# 20_Power_DC_IN.net
KiCad netlist of a schematic drawn in Altium Designer
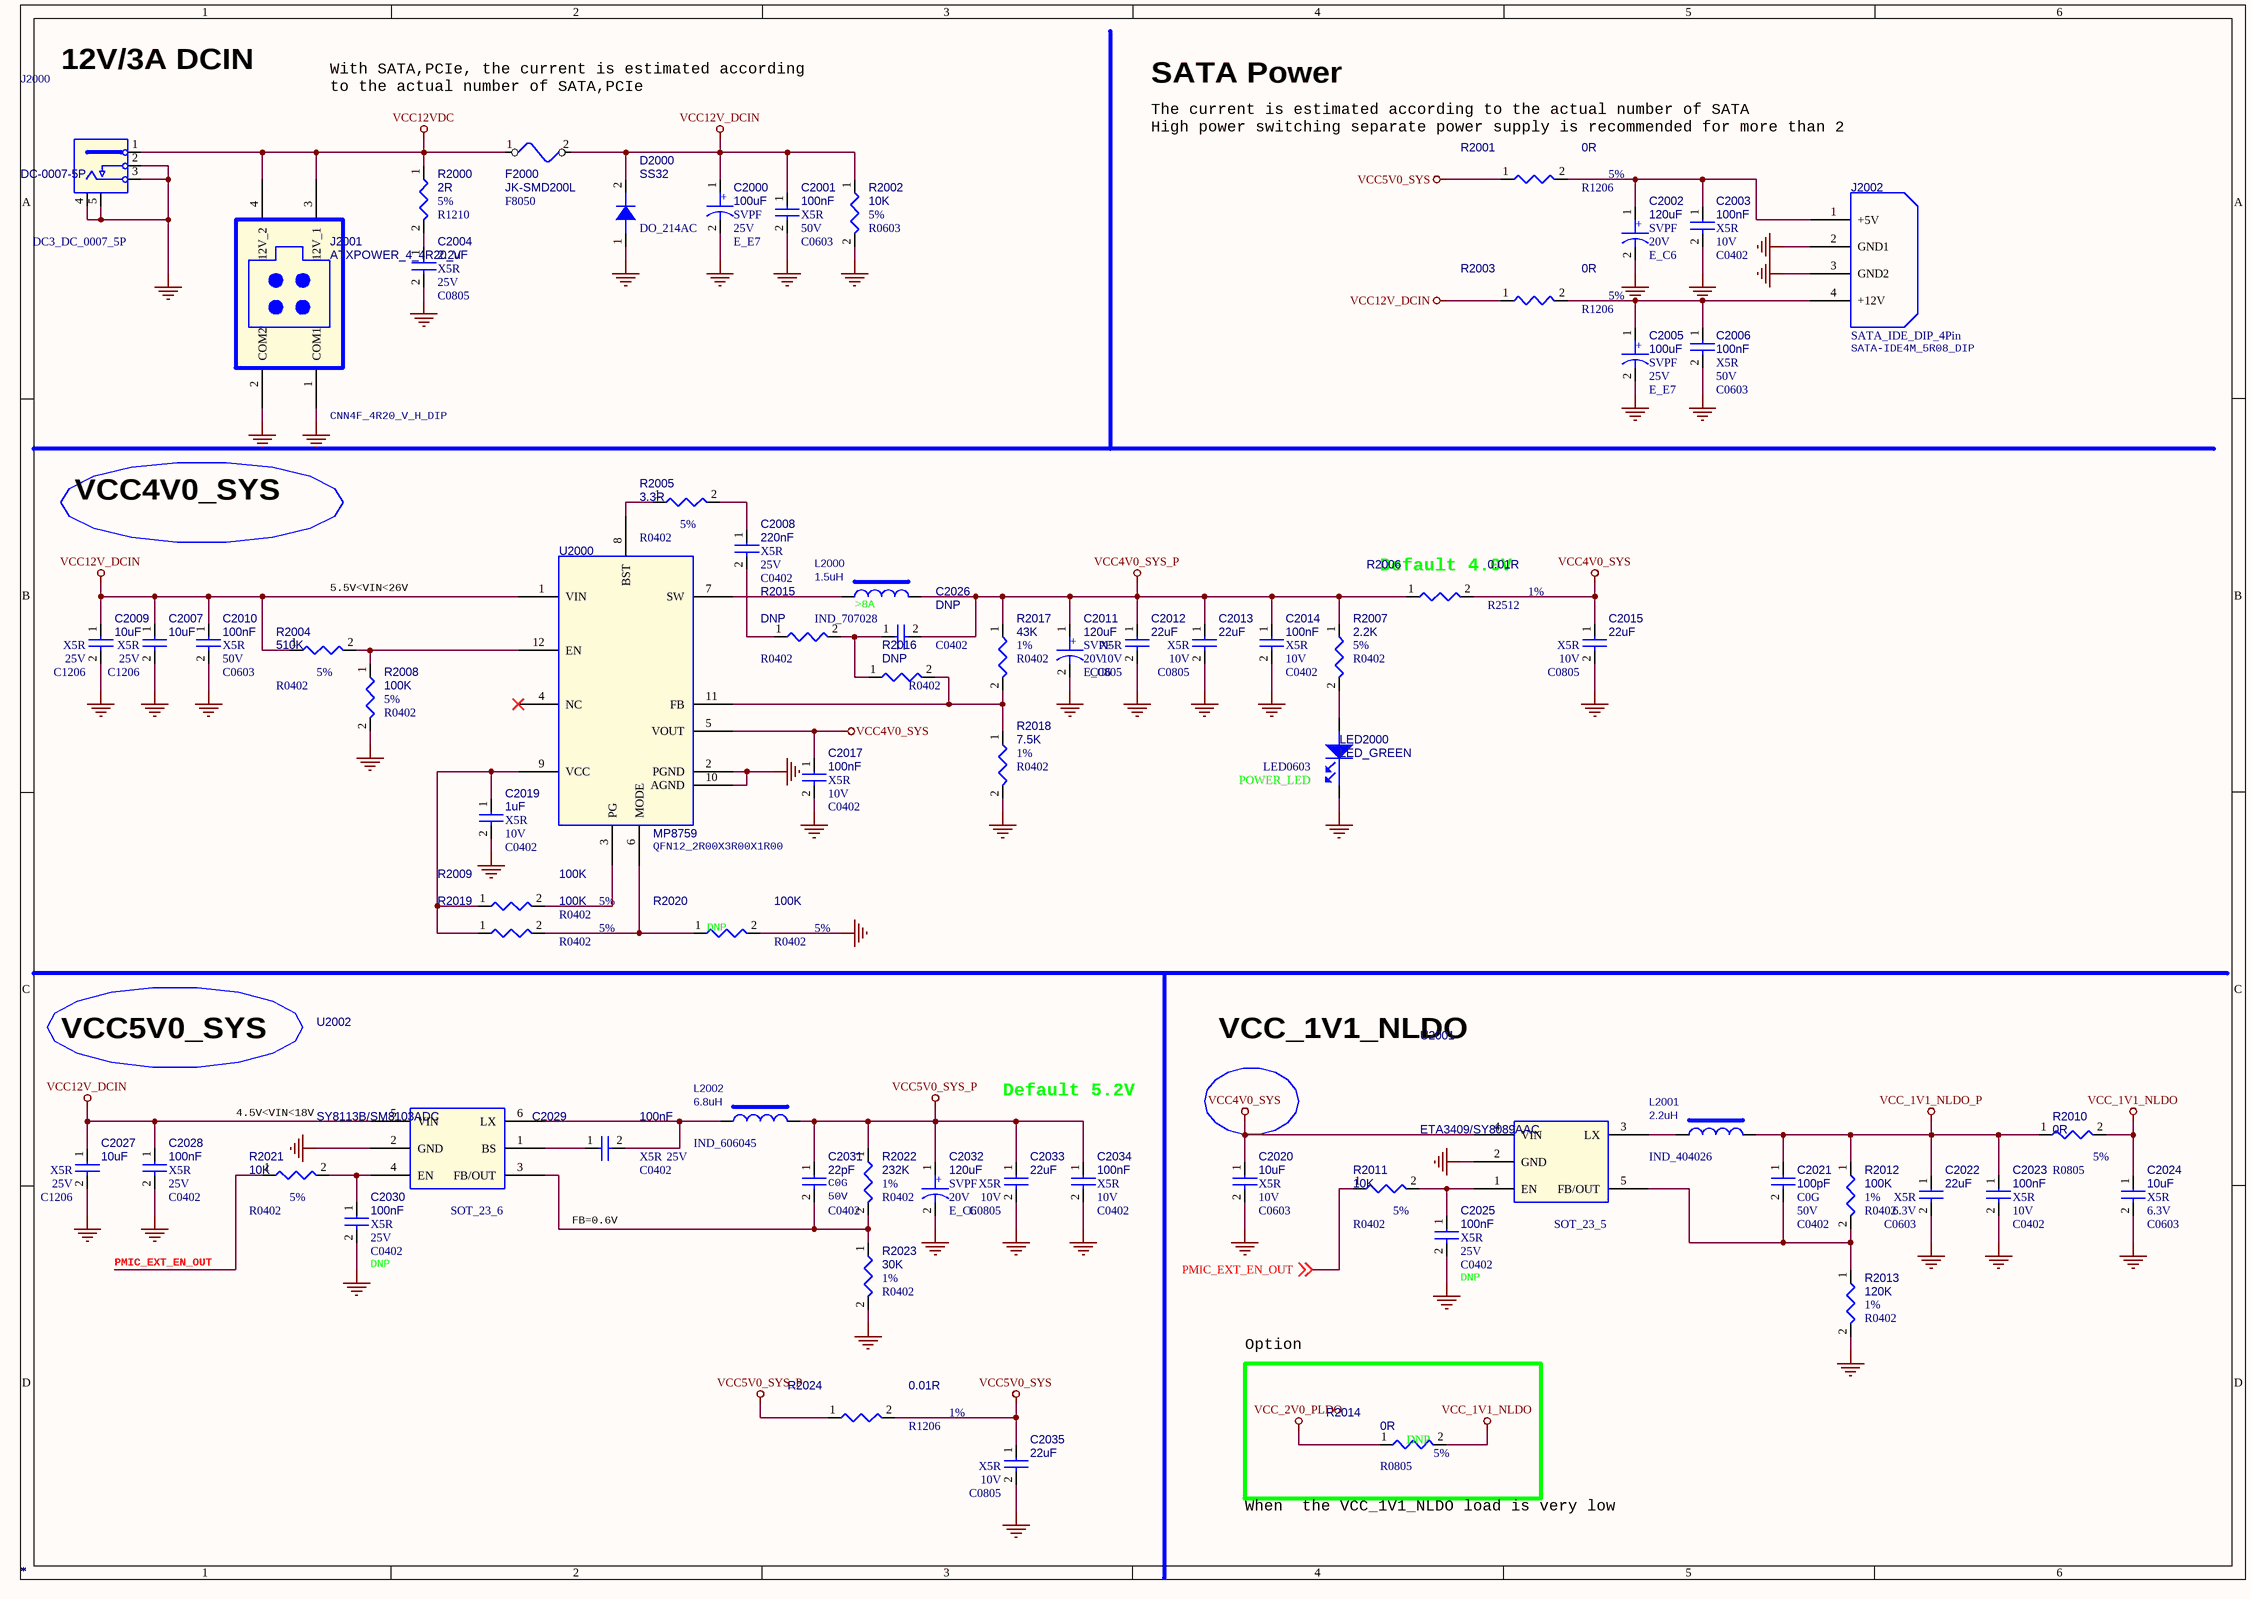
[diagram p0: 20.Power_DC IN.SchDoc]

(export (version "E")
  (design (tool "Eeschema 10.0.6"))
  (components
    (comp (ref "C2000")
      (value "*")
      (footprint "E_E7")
      (description "100uF,25V,24mR,SVPF")
      (fields
        (field (name "VOLTAGE") "25V")
        (field (name "DIELECTRIC") "SVPF")
        (field (name "PCB FOOTPRINT") "E_E7")
        (field (name "TOLERANCE") "20%")
        (field (name "MANUFACTURER") "Panasonic")
        (field (name "ALTIUM_UNNAMED_1") "100uF")
        (field (name "CREATED BY") "JJJ")
      )
      (libsource (lib "*") (part "CAP"))
    )
    (comp (ref "C2001")
      (value "*")
      (footprint "C0603")
      (description "cap,100.00nF,+/-10%,50V,X5R,C0603")
      (fields
        (field (name "VOLTAGE") "50V")
        (field (name "PCB FOOTPRINT") "C0603")
        (field (name "DIELECTRIC") "X5R")
        (field (name "MANUFACTURER") "TDK")
        (field (name "TOLERANCE") "10%")
        (field (name "ALTIUM_UNNAMED_1") "100nF")
        (field (name "CREATED BY") "JJJ")
      )
      (libsource (lib "*") (part "CAP NP"))
    )
    (comp (ref "C2002")
      (value "*")
      (footprint "E_C6")
      (description "120uF,20V,25mR,SVPF")
      (fields
        (field (name "VOLTAGE") "20V")
        (field (name "DIELECTRIC") "SVPF")
        (field (name "PCB FOOTPRINT") "E_C6")
        (field (name "MANUFACTURER") "Panasonic")
        (field (name "TOLERANCE") "20%")
        (field (name "ALTIUM_UNNAMED_1") "120uF")
        (field (name "CREATED BY") "JJJ")
      )
      (libsource (lib "*") (part "CAP"))
    )
    (comp (ref "C2003")
      (value "*")
      (footprint "C0402")
      (description "cap,100.00nF,+/-10%,10V,X5R,C0402")
      (fields
        (field (name "VOLTAGE") "10V")
        (field (name "PCB FOOTPRINT") "C0402")
        (field (name "DIELECTRIC") "X5R")
        (field (name "TOLERANCE") "10%")
        (field (name "MANUFACTURER") "TDK")
        (field (name "ALTIUM_UNNAMED_1") "100nF")
        (field (name "CREATED BY") "JJJ")
      )
      (libsource (lib "*") (part "CAP NP"))
    )
    (comp (ref "C2004")
      (value "*")
      (footprint "C0805")
      (description "cap,2.20uF,+/-10%,25V,X5R,C0805")
      (fields
        (field (name "VOLTAGE") "25V")
        (field (name "PCB FOOTPRINT") "C0805")
        (field (name "DIELECTRIC") "X5R")
        (field (name "TOLERANCE") "10%")
        (field (name "MANUFACTURER") "TDK")
        (field (name "ALTIUM_UNNAMED_1") "2.2uF")
        (field (name "CREATED BY") "JJJ")
      )
      (libsource (lib "*") (part "CAP NP"))
    )
    (comp (ref "C2005")
      (value "*")
      (footprint "E_E7")
      (description "100uF,25V,24mR,SVPF")
      (fields
        (field (name "VOLTAGE") "25V")
        (field (name "DIELECTRIC") "SVPF")
        (field (name "PCB FOOTPRINT") "E_E7")
        (field (name "MANUFACTURER") "Panasonic")
        (field (name "TOLERANCE") "20%")
        (field (name "ALTIUM_UNNAMED_1") "100uF")
        (field (name "CREATED BY") "JJJ")
      )
      (libsource (lib "*") (part "CAP"))
    )
    (comp (ref "C2006")
      (value "*")
      (footprint "C0603")
      (description "cap,100.00nF,+/-10%,50V,X5R,C0603")
      (fields
        (field (name "VOLTAGE") "50V")
        (field (name "PCB FOOTPRINT") "C0603")
        (field (name "DIELECTRIC") "X5R")
        (field (name "MANUFACTURER") "TDK")
        (field (name "TOLERANCE") "10%")
        (field (name "ALTIUM_UNNAMED_1") "100nF")
        (field (name "CREATED BY") "JJJ")
      )
      (libsource (lib "*") (part "CAP NP"))
    )
    (comp (ref "C2007")
      (value "*")
      (footprint "C1206")
      (description "cap,10.00uF,+/-10%,25V,X5R,C1206")
      (fields
        (field (name "VOLTAGE") "25V")
        (field (name "PCB FOOTPRINT") "C1206")
        (field (name "DIELECTRIC") "X5R")
        (field (name "MANUFACTURER") "TDK")
        (field (name "TOLERANCE") "10%")
        (field (name "ALTIUM_UNNAMED_1") "10uF")
        (field (name "CREATED BY") "JJJ")
      )
      (libsource (lib "*") (part "CAP NP"))
    )
    (comp (ref "C2008")
      (value "*")
      (footprint "C0402")
      (description "cap,220.00nF,+/-10%,25V,X5R,C0402")
      (fields
        (field (name "VOLTAGE") "25V")
        (field (name "PCB FOOTPRINT") "C0402")
        (field (name "DIELECTRIC") "X5R")
        (field (name "MANUFACTURER") "TDK")
        (field (name "TOLERANCE") "10%")
        (field (name "ALTIUM_UNNAMED_1") "220nF")
        (field (name "CREATED BY") "JJJ")
      )
      (libsource (lib "*") (part "CAP NP"))
    )
    (comp (ref "C2009")
      (value "*")
      (footprint "C1206")
      (description "cap,10.00uF,+/-10%,25V,X5R,C1206")
      (fields
        (field (name "VOLTAGE") "25V")
        (field (name "PCB FOOTPRINT") "C1206")
        (field (name "DIELECTRIC") "X5R")
        (field (name "MANUFACTURER") "TDK")
        (field (name "TOLERANCE") "10%")
        (field (name "ALTIUM_UNNAMED_1") "10uF")
        (field (name "CREATED BY") "JJJ")
      )
      (libsource (lib "*") (part "CAP NP"))
    )
    (comp (ref "C2010")
      (value "*")
      (footprint "C0603")
      (description "cap,100.00nF,+/-10%,50V,X5R,C0603")
      (fields
        (field (name "VOLTAGE") "50V")
        (field (name "PCB FOOTPRINT") "C0603")
        (field (name "DIELECTRIC") "X5R")
        (field (name "MANUFACTURER") "TDK")
        (field (name "TOLERANCE") "10%")
        (field (name "ALTIUM_UNNAMED_1") "100nF")
        (field (name "CREATED BY") "JJJ")
      )
      (libsource (lib "*") (part "CAP NP"))
    )
    (comp (ref "C2011")
      (value "*")
      (footprint "E_C6")
      (description "120uF,20V,25mR,SVPF")
      (fields
        (field (name "VOLTAGE") "20V")
        (field (name "DIELECTRIC") "SVPF")
        (field (name "PCB FOOTPRINT") "E_C6")
        (field (name "MANUFACTURER") "Panasonic")
        (field (name "TOLERANCE") "20%")
        (field (name "ALTIUM_UNNAMED_1") "120uF")
        (field (name "CREATED BY") "JJJ")
      )
      (libsource (lib "*") (part "CAP"))
    )
    (comp (ref "C2012")
      (value "*")
      (footprint "C0805")
      (description "cap,22.00uF,+/-10%,10V,X5R,C0805")
      (fields
        (field (name "VOLTAGE") "10V")
        (field (name "PCB FOOTPRINT") "C0805")
        (field (name "DIELECTRIC") "X5R")
        (field (name "TOLERANCE") "10%")
        (field (name "MANUFACTURER") "TDK")
        (field (name "ALTIUM_UNNAMED_1") "22uF")
        (field (name "CREATED BY") "JJJ")
      )
      (libsource (lib "*") (part "CAP NP"))
    )
    (comp (ref "C2013")
      (value "*")
      (footprint "C0805")
      (description "cap,22.00uF,+/-10%,10V,X5R,C0805")
      (fields
        (field (name "VOLTAGE") "10V")
        (field (name "PCB FOOTPRINT") "C0805")
        (field (name "DIELECTRIC") "X5R")
        (field (name "MANUFACTURER") "TDK")
        (field (name "TOLERANCE") "10%")
        (field (name "ALTIUM_UNNAMED_1") "22uF")
        (field (name "CREATED BY") "JJJ")
      )
      (libsource (lib "*") (part "CAP NP"))
    )
    (comp (ref "C2014")
      (value "*")
      (footprint "C0402")
      (description "cap,100.00nF,+/-10%,10V,X5R,C0402")
      (fields
        (field (name "VOLTAGE") "10V")
        (field (name "PCB FOOTPRINT") "C0402")
        (field (name "DIELECTRIC") "X5R")
        (field (name "MANUFACTURER") "TDK")
        (field (name "TOLERANCE") "10%")
        (field (name "ALTIUM_UNNAMED_1") "100nF")
        (field (name "CREATED BY") "JJJ")
      )
      (libsource (lib "*") (part "CAP NP"))
    )
    (comp (ref "C2015")
      (value "*")
      (footprint "C0805")
      (description "cap,22.00uF,+/-10%,10V,X5R,C0805")
      (fields
        (field (name "VOLTAGE") "10V")
        (field (name "PCB FOOTPRINT") "C0805")
        (field (name "DIELECTRIC") "X5R")
        (field (name "MANUFACTURER") "TDK")
        (field (name "TOLERANCE") "10%")
        (field (name "ALTIUM_UNNAMED_1") "22uF")
        (field (name "CREATED BY") "JJJ")
      )
      (libsource (lib "*") (part "CAP NP"))
    )
    (comp (ref "C2017")
      (value "*")
      (footprint "C0402")
      (description "cap,100.00nF,+/-10%,10V,X5R,C0402")
      (fields
        (field (name "VOLTAGE") "10V")
        (field (name "PCB FOOTPRINT") "C0402")
        (field (name "DIELECTRIC") "X5R")
        (field (name "TOLERANCE") "10%")
        (field (name "MANUFACTURER") "TDK")
        (field (name "ALTIUM_UNNAMED_1") "100nF")
        (field (name "CREATED BY") "JJJ")
      )
      (libsource (lib "*") (part "CAP NP"))
    )
    (comp (ref "C2019")
      (value "*")
      (footprint "C0402")
      (description "cap,1.00uF,+/-10%,10V,X5R,C0402")
      (fields
        (field (name "VOLTAGE") "10V")
        (field (name "PCB FOOTPRINT") "C0402")
        (field (name "DIELECTRIC") "X5R")
        (field (name "MANUFACTURER") "TDK")
        (field (name "TOLERANCE") "10%")
        (field (name "ALTIUM_UNNAMED_1") "1uF")
        (field (name "CREATED BY") "JJJ")
      )
      (libsource (lib "*") (part "CAP NP"))
    )
    (comp (ref "C2020")
      (value "*")
      (footprint "C0603")
      (description "cap,10.00uF,+/-10%,10V,X5R,C0603")
      (fields
        (field (name "VOLTAGE") "10V")
        (field (name "PCB FOOTPRINT") "C0603")
        (field (name "DIELECTRIC") "X5R")
        (field (name "MANUFACTURER") "TDK")
        (field (name "TOLERANCE") "10%")
        (field (name "ALTIUM_UNNAMED_1") "10uF")
        (field (name "CREATED BY") "JJJ")
      )
      (libsource (lib "*") (part "CAP NP"))
    )
    (comp (ref "C2021")
      (value "*")
      (footprint "C0402")
      (description "cap,100.00pF,+/-10%,50V,C0G,C0402")
      (fields
        (field (name "VOLTAGE") "50V")
        (field (name "PCB FOOTPRINT") "C0402")
        (field (name "DIELECTRIC") "C0G")
        (field (name "MANUFACTURER") "TDK")
        (field (name "TOLERANCE") "10%")
        (field (name "ALTIUM_UNNAMED_1") "100pF")
        (field (name "CREATED BY") "JJJ")
      )
      (libsource (lib "*") (part "CAP NP"))
    )
    (comp (ref "C2022")
      (value "*")
      (footprint "C0603")
      (description "cap,22.00uF,+/-20%,6.3V,X5R,C0603")
      (fields
        (field (name "VOLTAGE") "6.3V")
        (field (name "PCB FOOTPRINT") "C0603")
        (field (name "DIELECTRIC") "X5R")
        (field (name "TOLERANCE") "20%")
        (field (name "MANUFACTURER") "TDK")
        (field (name "ALTIUM_UNNAMED_1") "22uF")
        (field (name "CREATED BY") "JJJ")
      )
      (libsource (lib "*") (part "CAP NP"))
    )
    (comp (ref "C2023")
      (value "*")
      (footprint "C0402")
      (description "cap,100.00nF,+/-10%,10V,X5R,C0402")
      (fields
        (field (name "VOLTAGE") "10V")
        (field (name "PCB FOOTPRINT") "C0402")
        (field (name "DIELECTRIC") "X5R")
        (field (name "MANUFACTURER") "TDK")
        (field (name "TOLERANCE") "10%")
        (field (name "ALTIUM_UNNAMED_1") "100nF")
        (field (name "CREATED BY") "JJJ")
      )
      (libsource (lib "*") (part "CAP NP"))
    )
    (comp (ref "C2024")
      (value "*")
      (footprint "C0603")
      (description "cap,10.00uF,+/-10%,6.3V,X5R,C0603")
      (fields
        (field (name "VOLTAGE") "6.3V")
        (field (name "PCB FOOTPRINT") "C0603")
        (field (name "DIELECTRIC") "X5R")
        (field (name "MANUFACTURER") "TDK")
        (field (name "TOLERANCE") "10%")
        (field (name "ALTIUM_UNNAMED_1") "10uF")
        (field (name "CREATED BY") "JJJ")
      )
      (libsource (lib "*") (part "CAP NP"))
    )
    (comp (ref "C2025")
      (value "*")
      (footprint "C0402")
      (description "cap,100.00nF,+/-10%,25V,X5R,C0402")
      (fields
        (field (name "VOLTAGE") "25V")
        (field (name "PCB FOOTPRINT") "C0402")
        (field (name "DIELECTRIC") "X5R")
        (field (name "OPTION") "DNP")
        (field (name "TOLERANCE") "10%")
        (field (name "MANUFACTURER") "TDK")
        (field (name "ALTIUM_UNNAMED_1") "100nF")
        (field (name "CREATED BY") "JJJ")
      )
      (libsource (lib "*") (part "CAP NP"))
    )
    (comp (ref "C2026")
      (value "*")
      (footprint "C0402")
      (description "Did Not Place.")
      (fields
        (field (name "PCB FOOTPRINT") "C0402")
        (field (name "ALTIUM_UNNAMED_1") "DNP")
        (field (name "CREATED BY") "JJJ")
      )
      (libsource (lib "*") (part "CAP NP"))
    )
    (comp (ref "C2027")
      (value "*")
      (footprint "C1206")
      (description "cap,10.00uF,+/-10%,25V,X5R,C1206")
      (fields
        (field (name "VOLTAGE") "25V")
        (field (name "PCB FOOTPRINT") "C1206")
        (field (name "DIELECTRIC") "X5R")
        (field (name "TOLERANCE") "10%")
        (field (name "MANUFACTURER") "TDK")
        (field (name "ALTIUM_UNNAMED_1") "10uF")
        (field (name "CREATED BY") "JJJ")
      )
      (libsource (lib "*") (part "CAP NP"))
    )
    (comp (ref "C2028")
      (value "*")
      (footprint "C0402")
      (description "cap,100.00nF,+/-10%,25V,X5R,C0402")
      (fields
        (field (name "VOLTAGE") "25V")
        (field (name "PCB FOOTPRINT") "C0402")
        (field (name "DIELECTRIC") "X5R")
        (field (name "MANUFACTURER") "TDK")
        (field (name "TOLERANCE") "10%")
        (field (name "ALTIUM_UNNAMED_1") "100nF")
        (field (name "CREATED BY") "JJJ")
      )
      (libsource (lib "*") (part "CAP NP"))
    )
    (comp (ref "C2029")
      (value "*")
      (footprint "C0402")
      (description "cap,100.00nF,+/-10%,25V,X5R,C0402")
      (fields
        (field (name "VOLTAGE") "25V")
        (field (name "PCB FOOTPRINT") "C0402")
        (field (name "DIELECTRIC") "X5R")
        (field (name "MANUFACTURER") "TDK")
        (field (name "TOLERANCE") "10%")
        (field (name "ALTIUM_UNNAMED_1") "100nF")
        (field (name "CREATED BY") "JJJ")
      )
      (libsource (lib "*") (part "CAP NP"))
    )
    (comp (ref "C2030")
      (value "*")
      (footprint "C0402")
      (description "cap,100.00nF,+/-10%,25V,X5R,C0402")
      (fields
        (field (name "VOLTAGE") "25V")
        (field (name "PCB FOOTPRINT") "C0402")
        (field (name "DIELECTRIC") "X5R")
        (field (name "OPTION") "DNP")
        (field (name "TOLERANCE") "10%")
        (field (name "MANUFACTURER") "TDK")
        (field (name "ALTIUM_UNNAMED_1") "100nF")
        (field (name "CREATED BY") "JJJ")
      )
      (libsource (lib "*") (part "CAP NP"))
    )
    (comp (ref "C2031")
      (value "*")
      (footprint "C0402")
      (description "cap,22.00pF,+/-5%,50V,C0G,C0402")
      (fields
        (field (name "VOLTAGE") "50V")
        (field (name "PCB FOOTPRINT") "C0402")
        (field (name "DIELECTRIC") "C0G")
        (field (name "TOLERANCE") "5%")
        (field (name "MANUFACTURER") "TDK")
        (field (name "ALTIUM_UNNAMED_1") "22pF")
        (field (name "CREATED BY") "JJJ")
      )
      (libsource (lib "*") (part "CAP NP"))
    )
    (comp (ref "C2032")
      (value "*")
      (footprint "E_C6")
      (description "120uF,20V,25mR,SVPF")
      (fields
        (field (name "VOLTAGE") "20V")
        (field (name "DIELECTRIC") "SVPF")
        (field (name "PCB FOOTPRINT") "E_C6")
        (field (name "TOLERANCE") "20%")
        (field (name "MANUFACTURER") "Panasonic")
        (field (name "ALTIUM_UNNAMED_1") "120uF")
        (field (name "CREATED BY") "JJJ")
      )
      (libsource (lib "*") (part "CAP"))
    )
    (comp (ref "C2033")
      (value "*")
      (footprint "C0805")
      (description "cap,22.00uF,+/-10%,10V,X5R,C0805")
      (fields
        (field (name "VOLTAGE") "10V")
        (field (name "PCB FOOTPRINT") "C0805")
        (field (name "DIELECTRIC") "X5R")
        (field (name "TOLERANCE") "10%")
        (field (name "MANUFACTURER") "TDK")
        (field (name "ALTIUM_UNNAMED_1") "22uF")
        (field (name "CREATED BY") "JJJ")
      )
      (libsource (lib "*") (part "CAP NP"))
    )
    (comp (ref "C2034")
      (value "*")
      (footprint "C0402")
      (description "cap,100.00nF,+/-10%,10V,X5R,C0402")
      (fields
        (field (name "VOLTAGE") "10V")
        (field (name "PCB FOOTPRINT") "C0402")
        (field (name "DIELECTRIC") "X5R")
        (field (name "TOLERANCE") "10%")
        (field (name "MANUFACTURER") "TDK")
        (field (name "ALTIUM_UNNAMED_1") "100nF")
        (field (name "CREATED BY") "JJJ")
      )
      (libsource (lib "*") (part "CAP NP"))
    )
    (comp (ref "C2035")
      (value "*")
      (footprint "C0805")
      (description "cap,22.00uF,+/-10%,10V,X5R,C0805")
      (fields
        (field (name "VOLTAGE") "10V")
        (field (name "PCB FOOTPRINT") "C0805")
        (field (name "DIELECTRIC") "X5R")
        (field (name "TOLERANCE") "10%")
        (field (name "MANUFACTURER") "TDK")
        (field (name "ALTIUM_UNNAMED_1") "22uF")
        (field (name "CREATED BY") "JJJ")
      )
      (libsource (lib "*") (part "CAP NP"))
    )
    (comp (ref "D2000")
      (value "*")
      (footprint "DO_214AC")
      (description "Schottky BarrierЈ¬SS32 DO214AC")
      (fields
        (field (name "PCB FOOTPRINT") "DO_214AC")
        (field (name "MANUFACTURER") "РЗєЈ")
        (field (name "ALTIUM_UNNAMED_1") "SS32")
        (field (name "CREATED BY") "JJJ")
      )
      (libsource (lib "*") (part "DIODE"))
    )
    (comp (ref "F2000")
      (value "*")
      (footprint "F8050")
      (description "±ЈПХЛїЈ¬Vmax=16V,Imax=100AЈ¬Icurrent=8A,Ri=0.028ohm")
      (fields
        (field (name "PCB FOOTPRINT") "F8050")
        (field (name "MANUFACTURER") "ЅрИрµзЧУ")
        (field (name "MANUFACTURER PART NUMBER") "Q/JKTD-16-200")
        (field (name "ALTIUM_UNNAMED_1") "JK-SMD200L")
        (field (name "CREATED BY") "JJJ")
      )
      (libsource (lib "*") (part "FUSE"))
    )
    (comp (ref "J2000")
      (value "*")
      (footprint "DC3_DC_0007_5P")
      (description "DCЧщ")
      (fields
        (field (name "PCB FOOTPRINT") "DC3_DC_0007_5P")
        (field (name "MANUFACTURER") "НъїЖґп")
        (field (name "MANUFACTURER PART NUMBER") "DC-0007-5P")
        (field (name "ALTIUM_UNNAMED_1") "DC-0007-5P")
        (field (name "CREATED BY") "JJJ")
      )
      (libsource (lib "*") (part "DCJACK_3P"))
    )
    (comp (ref "J2001")
      (value "*")
      (footprint "CNN4F_4R20_V_H_DIP")
      (fields
        (field (name "PCB FOOTPRINT") "CNN4F_4R20_V_H_DIP")
        (field (name "ALTIUM_UNNAMED_1") "ATXPOWER_4_4R20_V")
      )
      (libsource (lib "*") (part "CON4_8"))
    )
    (comp (ref "J2002")
      (value "*")
      (footprint "SATA-IDE4M_5R08_DIP")
      (fields
        (field (name "PCB FOOTPRINT") "SATA-IDE4M_5R08_DIP")
        (field (name "ALTIUM_UNNAMED_1") "SATA_IDE_DIP_4Pin")
      )
      (libsource (lib "*") (part "SATA_IDE_DIP_0"))
    )
    (comp (ref "L2000")
      (value "*")
      (footprint "IND_707028")
      (description "Power Inductor,1.5uH,MWSA0603S-1R5MT")
      (fields
        (field (name "PCB FOOTPRINT") "IND_707028")
        (field (name "TOLERANCE") "20%")
        (field (name "MANUFACTURER") "Vishay")
        (field (name "OPTION") ">8A")
        (field (name "ALTIUM_UNNAMED_1") "1.5uH")
        (field (name "CREATED BY") "JJJ")
      )
      (libsource (lib "*") (part "INDUCTORS OF FERRITE_Dup1"))
    )
    (comp (ref "L2001")
      (value "*")
      (footprint "IND_404026")
      (description "Power Inductor,2.2uH,0.2,IND_404026")
      (fields
        (field (name "PCB FOOTPRINT") "IND_404026")
        (field (name "MANUFACTURER") "sunlord")
        (field (name "TOLERANCE") "20%")
        (field (name "ALTIUM_UNNAMED_1") "2.2uH")
        (field (name "CREATED BY") "YTL")
      )
      (libsource (lib "*") (part "INDUCTORS OF FERRITE_Dup1"))
    )
    (comp (ref "L2002")
      (value "*")
      (footprint "IND_606045")
      (description "Power Inductor,6.8uH,0.031,IND_606045")
      (fields
        (field (name "PCB FOOTPRINT") "IND_606045")
        (field (name "TOLERANCE") "20%")
        (field (name "MANUFACTURER") "sunlord")
        (field (name "ALTIUM_UNNAMED_1") "6.8uH")
        (field (name "CREATED BY") "YWQ")
      )
      (libsource (lib "*") (part "INDUCTORS OF FERRITE_Dup1"))
    )
    (comp (ref "LED2000")
      (value "*")
      (footprint "LED0603")
      (description "МщЖ¬LEDµЖЈ¬0603Ј¬ВМЙ«")
      (fields
        (field (name "PCB FOOTPRINT") "LED0603")
        (field (name "OPTION") "POWER_LED")
        (field (name "ALTIUM_UNNAMED_1") "LED_GREEN")
        (field (name "CREATED BY") "JJJ")
      )
      (libsource (lib "*") (part "LED"))
    )
    (comp (ref "R2000")
      (value "*")
      (footprint "R0402")
      (description "НЁУГєсД¤µзЧи,2R,+/-5%,R1210,1/2W.")
      (fields
        (field (name "PCB FOOTPRINT") "R1210")
        (field (name "TOLERANCE") "5%")
        (field (name "MANUFACTURER") "YAGEO")
        (field (name "ALTIUM_UNNAMED_1") "2R")
        (field (name "CREATED BY") "YTL")
      )
      (libsource (lib "*") (part "RESISTOR_Dup1"))
    )
    (comp (ref "R2001")
      (value "*")
      (footprint "R0402")
      (description "НЁУГєсД¤µзЧи,0R,+/-5%,R1206,1/4W.")
      (fields
        (field (name "PCB FOOTPRINT") "R1206")
        (field (name "TOLERANCE") "5%")
        (field (name "MANUFACTURER") "YAGEO")
        (field (name "ALTIUM_UNNAMED_1") "0R")
        (field (name "CREATED BY") "YTL")
      )
      (libsource (lib "*") (part "RESISTOR_Dup1"))
    )
    (comp (ref "R2002")
      (value "*")
      (footprint "R0402")
      (description "НЁУГєсД¤µзЧи,10K,+/-5%,R0603,1/10W.")
      (fields
        (field (name "PCB FOOTPRINT") "R0603")
        (field (name "TOLERANCE") "5%")
        (field (name "MANUFACTURER") "YAGEO")
        (field (name "ALTIUM_UNNAMED_1") "10K")
        (field (name "CREATED BY") "YTL")
      )
      (libsource (lib "*") (part "RESISTOR_Dup1"))
    )
    (comp (ref "R2003")
      (value "*")
      (footprint "R0402")
      (description "НЁУГєсД¤µзЧи,0R,+/-5%,R1206,1/4W.")
      (fields
        (field (name "PCB FOOTPRINT") "R1206")
        (field (name "TOLERANCE") "5%")
        (field (name "MANUFACTURER") "YAGEO")
        (field (name "ALTIUM_UNNAMED_1") "0R")
        (field (name "CREATED BY") "YTL")
      )
      (libsource (lib "*") (part "RESISTOR_Dup1"))
    )
    (comp (ref "R2004")
      (value "*")
      (footprint "R0402")
      (description "НЁУГєсД¤µзЧи,510K,+/-5%,R0402,1/16W.")
      (fields
        (field (name "PCB FOOTPRINT") "R0402")
        (field (name "TOLERANCE") "5%")
        (field (name "MANUFACTURER") "YAGEO")
        (field (name "ALTIUM_UNNAMED_1") "510K")
        (field (name "CREATED BY") "YTL")
      )
      (libsource (lib "*") (part "RESISTOR_Dup1"))
    )
    (comp (ref "R2005")
      (value "*")
      (footprint "R0402")
      (description "НЁУГєсД¤µзЧи,3R3,+/-5%,R0402,1/16W.")
      (fields
        (field (name "PCB FOOTPRINT") "R0402")
        (field (name "TOLERANCE") "5%")
        (field (name "MANUFACTURER") "YAGEO")
        (field (name "ALTIUM_UNNAMED_1") "3.3R")
        (field (name "CREATED BY") "YTL")
      )
      (libsource (lib "*") (part "RESISTOR_Dup1"))
    )
    (comp (ref "R2006")
      (value "*")
      (footprint "R0402")
      (description "єсД¤µНЧиЦµµзЧи,0R01,+/-1%,R2512,1W.")
      (fields
        (field (name "PCB FOOTPRINT") "R2512")
        (field (name "TOLERANCE") "1%")
        (field (name "MANUFACTURER") "YAGEO")
        (field (name "ALTIUM_UNNAMED_1") "0.01R")
        (field (name "CREATED BY") "YTL")
      )
      (libsource (lib "*") (part "RESISTOR_Dup1"))
    )
    (comp (ref "R2007")
      (value "*")
      (footprint "R0402")
      (description "НЁУГєсД¤µзЧи,2K2,+/-5%,R0402,1/16W.")
      (fields
        (field (name "PCB FOOTPRINT") "R0402")
        (field (name "TOLERANCE") "5%")
        (field (name "MANUFACTURER") "YAGEO")
        (field (name "ALTIUM_UNNAMED_1") "2.2K")
        (field (name "CREATED BY") "YTL")
      )
      (libsource (lib "*") (part "RESISTOR_Dup1"))
    )
    (comp (ref "R2008")
      (value "*")
      (footprint "R0402")
      (description "НЁУГєсД¤µзЧи,100K,+/-5%,R0402,1/16W.")
      (fields
        (field (name "PCB FOOTPRINT") "R0402")
        (field (name "TOLERANCE") "5%")
        (field (name "MANUFACTURER") "YAGEO")
        (field (name "ALTIUM_UNNAMED_1") "100K")
        (field (name "CREATED BY") "YTL")
      )
      (libsource (lib "*") (part "RESISTOR_Dup1"))
    )
    (comp (ref "R2009")
      (value "*")
      (footprint "R0402")
      (description "НЁУГєсД¤µзЧи,100K,+/-5%,R0402,1/16W.")
      (fields
        (field (name "PCB FOOTPRINT") "R0402")
        (field (name "TOLERANCE") "5%")
        (field (name "MANUFACTURER") "YAGEO")
        (field (name "ALTIUM_UNNAMED_1") "100K")
        (field (name "CREATED BY") "YTL")
      )
      (libsource (lib "*") (part "RESISTOR_Dup1"))
    )
    (comp (ref "R2010")
      (value "*")
      (footprint "R0402")
      (description "НЁУГєсД¤µзЧи,0R,+/-5%,R0805,1/8W.")
      (fields
        (field (name "PCB FOOTPRINT") "R0805")
        (field (name "TOLERANCE") "5%")
        (field (name "MANUFACTURER") "YAGEO")
        (field (name "ALTIUM_UNNAMED_1") "0R")
        (field (name "CREATED BY") "YTL")
      )
      (libsource (lib "*") (part "RESISTOR_Dup1"))
    )
    (comp (ref "R2011")
      (value "*")
      (footprint "R0402")
      (description "НЁУГєсД¤µзЧи,10K,+/-5%,R0402,1/16W.")
      (fields
        (field (name "PCB FOOTPRINT") "R0402")
        (field (name "TOLERANCE") "5%")
        (field (name "MANUFACTURER") "YAGEO")
        (field (name "ALTIUM_UNNAMED_1") "10K")
        (field (name "CREATED BY") "YTL")
      )
      (libsource (lib "*") (part "RESISTOR_Dup1"))
    )
    (comp (ref "R2012")
      (value "*")
      (footprint "R0402")
      (description "НЁУГєсД¤µзЧи,100K,+/-1%,R0402,1/16W.")
      (fields
        (field (name "PCB FOOTPRINT") "R0402")
        (field (name "TOLERANCE") "1%")
        (field (name "MANUFACTURER") "YAGEO")
        (field (name "ALTIUM_UNNAMED_1") "100K")
        (field (name "CREATED BY") "YTL")
      )
      (libsource (lib "*") (part "RESISTOR_Dup1"))
    )
    (comp (ref "R2013")
      (value "*")
      (footprint "R0402")
      (description "НЁУГєсД¤µзЧи,120K,+/-1%,R0402,1/16W.")
      (fields
        (field (name "PCB FOOTPRINT") "R0402")
        (field (name "TOLERANCE") "1%")
        (field (name "MANUFACTURER") "YAGEO")
        (field (name "ALTIUM_UNNAMED_1") "120K")
        (field (name "CREATED BY") "YTL")
      )
      (libsource (lib "*") (part "RESISTOR_Dup1"))
    )
    (comp (ref "R2014")
      (value "*")
      (footprint "R0402")
      (description "НЁУГєсД¤µзЧи,0R,+/-5%,R0805,1/8W.")
      (fields
        (field (name "PCB FOOTPRINT") "R0805")
        (field (name "TOLERANCE") "5%")
        (field (name "MANUFACTURER") "YAGEO")
        (field (name "OPTION") "DNP")
        (field (name "ALTIUM_UNNAMED_1") "0R")
        (field (name "CREATED BY") "YTL")
      )
      (libsource (lib "*") (part "RESISTOR_Dup1"))
    )
    (comp (ref "R2015")
      (value "*")
      (footprint "R0402")
      (description "Did Not Place.")
      (fields
        (field (name "PCB FOOTPRINT") "R0402")
        (field (name "ALTIUM_UNNAMED_1") "DNP")
        (field (name "CREATED BY") "JJJ")
      )
      (libsource (lib "*") (part "RESISTOR_Dup1"))
    )
    (comp (ref "R2016")
      (value "*")
      (footprint "R0402")
      (description "Did Not Place.")
      (fields
        (field (name "PCB FOOTPRINT") "R0402")
        (field (name "ALTIUM_UNNAMED_1") "DNP")
        (field (name "CREATED BY") "JJJ")
      )
      (libsource (lib "*") (part "RESISTOR_Dup1"))
    )
    (comp (ref "R2017")
      (value "*")
      (footprint "R0402")
      (description "НЁУГєсД¤µзЧи,43K,+/-1%,R0402,1/16W.")
      (fields
        (field (name "PCB FOOTPRINT") "R0402")
        (field (name "TOLERANCE") "1%")
        (field (name "MANUFACTURER") "YAGEO")
        (field (name "ALTIUM_UNNAMED_1") "43K")
        (field (name "CREATED BY") "YTL")
      )
      (libsource (lib "*") (part "RESISTOR_Dup1"))
    )
    (comp (ref "R2018")
      (value "*")
      (footprint "R0402")
      (description "НЁУГєсД¤µзЧи,7K5,+/-1%,R0402,1/16W.")
      (fields
        (field (name "PCB FOOTPRINT") "R0402")
        (field (name "TOLERANCE") "1%")
        (field (name "MANUFACTURER") "YAGEO")
        (field (name "ALTIUM_UNNAMED_1") "7.5K")
        (field (name "CREATED BY") "YTL")
      )
      (libsource (lib "*") (part "RESISTOR_Dup1"))
    )
    (comp (ref "R2019")
      (value "*")
      (footprint "R0402")
      (description "НЁУГєсД¤µзЧи,100K,+/-5%,R0402,1/16W.")
      (fields
        (field (name "PCB FOOTPRINT") "R0402")
        (field (name "TOLERANCE") "5%")
        (field (name "MANUFACTURER") "YAGEO")
        (field (name "ALTIUM_UNNAMED_1") "100K")
        (field (name "CREATED BY") "YTL")
      )
      (libsource (lib "*") (part "RESISTOR_Dup1"))
    )
    (comp (ref "R2020")
      (value "*")
      (footprint "R0402")
      (description "НЁУГєсД¤µзЧи,100K,+/-5%,R0402,1/16W.")
      (fields
        (field (name "PCB FOOTPRINT") "R0402")
        (field (name "TOLERANCE") "5%")
        (field (name "MANUFACTURER") "YAGEO")
        (field (name "OPTION") "DNP")
        (field (name "ALTIUM_UNNAMED_1") "100K")
        (field (name "CREATED BY") "YTL")
      )
      (libsource (lib "*") (part "RESISTOR_Dup1"))
    )
    (comp (ref "R2021")
      (value "*")
      (footprint "R0402")
      (description "НЁУГєсД¤µзЧи,10K,+/-5%,R0402,1/16W.")
      (fields
        (field (name "PCB FOOTPRINT") "R0402")
        (field (name "TOLERANCE") "5%")
        (field (name "MANUFACTURER") "YAGEO")
        (field (name "ALTIUM_UNNAMED_1") "10K")
        (field (name "CREATED BY") "YTL")
      )
      (libsource (lib "*") (part "RESISTOR_Dup1"))
    )
    (comp (ref "R2022")
      (value "*")
      (footprint "R0402")
      (description "НЁУГєсД¤µзЧи,232K,+/-1%,R0402,1/16W.")
      (fields
        (field (name "PCB FOOTPRINT") "R0402")
        (field (name "TOLERANCE") "1%")
        (field (name "MANUFACTURER") "YAGEO")
        (field (name "ALTIUM_UNNAMED_1") "232K")
        (field (name "CREATED BY") "YTL")
      )
      (libsource (lib "*") (part "RESISTOR_Dup1"))
    )
    (comp (ref "R2023")
      (value "*")
      (footprint "R0402")
      (description "НЁУГєсД¤µзЧи,30K,+/-1%,R0402,1/16W.")
      (fields
        (field (name "PCB FOOTPRINT") "R0402")
        (field (name "TOLERANCE") "1%")
        (field (name "MANUFACTURER") "YAGEO")
        (field (name "ALTIUM_UNNAMED_1") "30K")
        (field (name "CREATED BY") "YTL")
      )
      (libsource (lib "*") (part "RESISTOR_Dup1"))
    )
    (comp (ref "R2024")
      (value "*")
      (footprint "R0402")
      (description "єсД¤µНЧиЦµµзЧи,0R01,+/-1%,R1206,1/2W.")
      (fields
        (field (name "PCB FOOTPRINT") "R1206")
        (field (name "TOLERANCE") "1%")
        (field (name "MANUFACTURER") "YAGEO")
        (field (name "ALTIUM_UNNAMED_1") "0.01R")
        (field (name "CREATED BY") "YTL")
      )
      (libsource (lib "*") (part "RESISTOR_Dup1"))
    )
    (comp (ref "U2000")
      (value "*")
      (footprint "QFN12_2R00X3R00X1R00")
      (fields
        (field (name "PCB FOOTPRINT") "QFN12_2R00X3R00X1R00")
        (field (name "ALTIUM_UNNAMED_1") "MP8759")
      )
      (libsource (lib "*") (part "MP8759_6"))
    )
    (comp (ref "U2001")
      (value "*")
      (footprint "SOT_23_5")
      (description "High Efficiency 5.5V, 2A continuous, 3A peak, 1MHz Synchronous Step Down Regulator")
      (fields
        (field (name "PCB FOOTPRINT") "SOT_23_5")
        (field (name "MANUFACTURER") "SilergyЈЁОщБ¦ЅЬЈ©")
        (field (name "ALTIUM_UNNAMED_1") "ETA3409/SY8089AAC")
        (field (name "CREATED BY") "JJJ")
      )
      (libsource (lib "*") (part "DCDC_SY8088"))
    )
    (comp (ref "U2002")
      (value "*")
      (footprint "SOT_23_6")
      (fields
        (field (name "PCB FOOTPRINT") "SOT_23_6")
        (field (name "MANUFACTURER") "SilergyЈЁОщБ¦ЅЬЈ©")
        (field (name "ALTIUM_UNNAMED_1") "SY8113B/SM8103ADC")
        (field (name "CREATED BY") "JJJ")
      )
      (libsource (lib "*") (part "DCDC_SY8113"))
    )
  )
  (nets
    (net (code "1") (name "GND") (class "Default")
      (node (ref "C2000") (pin "2") (pinfunction "2_2") (pintype "passive"))
      (node (ref "C2001") (pin "2") (pinfunction "2_2") (pintype "passive"))
      (node (ref "C2002") (pin "2") (pinfunction "2_2") (pintype "passive"))
      (node (ref "C2003") (pin "2") (pinfunction "2_2") (pintype "passive"))
      (node (ref "C2004") (pin "2") (pinfunction "2_2") (pintype "passive"))
      (node (ref "C2005") (pin "2") (pinfunction "2_2") (pintype "passive"))
      (node (ref "C2006") (pin "2") (pinfunction "2_2") (pintype "passive"))
      (node (ref "C2007") (pin "2") (pinfunction "2_2") (pintype "passive"))
      (node (ref "C2009") (pin "2") (pinfunction "2_2") (pintype "passive"))
      (node (ref "C2010") (pin "2") (pinfunction "2_2") (pintype "passive"))
      (node (ref "C2011") (pin "2") (pinfunction "2_2") (pintype "passive"))
      (node (ref "C2012") (pin "2") (pinfunction "2_2") (pintype "passive"))
      (node (ref "C2013") (pin "2") (pinfunction "2_2") (pintype "passive"))
      (node (ref "C2014") (pin "2") (pinfunction "2_2") (pintype "passive"))
      (node (ref "C2015") (pin "2") (pinfunction "2_2") (pintype "passive"))
      (node (ref "C2017") (pin "2") (pinfunction "2_2") (pintype "passive"))
      (node (ref "C2019") (pin "2") (pinfunction "2_2") (pintype "passive"))
      (node (ref "C2020") (pin "2") (pinfunction "2_2") (pintype "passive"))
      (node (ref "C2022") (pin "2") (pinfunction "2_2") (pintype "passive"))
      (node (ref "C2023") (pin "2") (pinfunction "2_2") (pintype "passive"))
      (node (ref "C2024") (pin "2") (pinfunction "2_2") (pintype "passive"))
      (node (ref "C2025") (pin "2") (pinfunction "2_2") (pintype "passive"))
      (node (ref "C2027") (pin "2") (pinfunction "2_2") (pintype "passive"))
      (node (ref "C2028") (pin "2") (pinfunction "2_2") (pintype "passive"))
      (node (ref "C2030") (pin "2") (pinfunction "2_2") (pintype "passive"))
      (node (ref "C2032") (pin "2") (pinfunction "2_2") (pintype "passive"))
      (node (ref "C2033") (pin "2") (pinfunction "2_2") (pintype "passive"))
      (node (ref "C2034") (pin "2") (pinfunction "2_2") (pintype "passive"))
      (node (ref "C2035") (pin "2") (pinfunction "2_2") (pintype "passive"))
      (node (ref "D2000") (pin "1") (pinfunction "A_1") (pintype "passive"))
      (node (ref "J2000") (pin "2") (pinfunction "2_2") (pintype "passive"))
      (node (ref "J2000") (pin "3") (pinfunction "3_3") (pintype "passive"))
      (node (ref "J2000") (pin "4") (pinfunction "4_4") (pintype "passive"))
      (node (ref "J2000") (pin "5") (pinfunction "5_5") (pintype "passive"))
      (node (ref "J2001") (pin "1") (pinfunction "COM1_1") (pintype "passive"))
      (node (ref "J2001") (pin "2") (pinfunction "COM2_2") (pintype "passive"))
      (node (ref "J2002") (pin "2") (pinfunction "GND1_2") (pintype "passive"))
      (node (ref "J2002") (pin "3") (pinfunction "GND2_3") (pintype "passive"))
      (node (ref "LED2000") (pin "2") (pinfunction "CATHODE_2") (pintype "passive"))
      (node (ref "R2002") (pin "2") (pinfunction "2_2") (pintype "passive"))
      (node (ref "R2008") (pin "2") (pinfunction "2_2") (pintype "passive"))
      (node (ref "R2013") (pin "2") (pinfunction "2_2") (pintype "passive"))
      (node (ref "R2018") (pin "2") (pinfunction "2_2") (pintype "passive"))
      (node (ref "R2020") (pin "2") (pinfunction "2_2") (pintype "passive"))
      (node (ref "R2023") (pin "2") (pinfunction "2_2") (pintype "passive"))
      (node (ref "U2000") (pin "10") (pinfunction "AGND_10") (pintype "passive"))
      (node (ref "U2000") (pin "2") (pinfunction "PGND_2") (pintype "passive"))
      (node (ref "U2001") (pin "2") (pinfunction "GND_2") (pintype "passive"))
      (node (ref "U2002") (pin "2") (pinfunction "GND_2") (pintype "passive"))
    )
    (net (code "2") (name "Net-(C2004-Pad1)") (class "Default")
      (node (ref "C2004") (pin "1") (pinfunction "1_1") (pintype "passive"))
      (node (ref "R2000") (pin "2") (pinfunction "2_2") (pintype "passive"))
    )
    (net (code "3") (name "Net-(C2008-Pad1)") (class "Default")
      (node (ref "C2008") (pin "1") (pinfunction "1_1") (pintype "passive"))
      (node (ref "R2005") (pin "2") (pinfunction "2_2") (pintype "passive"))
    )
    (net (code "4") (name "Net-(C2008-Pad2)") (class "Default")
      (node (ref "C2008") (pin "2") (pinfunction "2_2") (pintype "passive"))
      (node (ref "R2015") (pin "1") (pinfunction "1_1") (pintype "passive"))
    )
    (net (code "5") (name "Net-(C2026-Pad1)") (class "Default")
      (node (ref "C2026") (pin "1") (pinfunction "1_1") (pintype "passive"))
      (node (ref "R2015") (pin "2") (pinfunction "2_2") (pintype "passive"))
      (node (ref "R2016") (pin "1") (pinfunction "1_1") (pintype "passive"))
    )
    (net (code "6") (name "Net-(J2002-+5V)") (class "Default")
      (node (ref "C2002") (pin "1") (pinfunction "1_1") (pintype "passive"))
      (node (ref "C2003") (pin "1") (pinfunction "1_1") (pintype "passive"))
      (node (ref "J2002") (pin "1") (pinfunction "+5V_1") (pintype "passive"))
      (node (ref "R2001") (pin "2") (pinfunction "2_2") (pintype "passive"))
    )
    (net (code "7") (name "Net-(J2002-+12V)") (class "Default")
      (node (ref "C2005") (pin "1") (pinfunction "1_1") (pintype "passive"))
      (node (ref "C2006") (pin "1") (pinfunction "1_1") (pintype "passive"))
      (node (ref "J2002") (pin "4") (pinfunction "+12V_4") (pintype "passive"))
      (node (ref "R2003") (pin "2") (pinfunction "2_2") (pintype "passive"))
    )
    (net (code "8") (name "Net-(LED2000-ANODE)") (class "Default")
      (node (ref "LED2000") (pin "1") (pinfunction "ANODE_1") (pintype "passive"))
      (node (ref "R2007") (pin "2") (pinfunction "2_2") (pintype "passive"))
    )
    (net (code "9") (name "Net-(U2000-BST)") (class "Default")
      (node (ref "R2005") (pin "1") (pinfunction "1_1") (pintype "passive"))
      (node (ref "U2000") (pin "8") (pinfunction "BST_8") (pintype "passive"))
    )
    (net (code "10") (name "Net-(U2000-EN)") (class "Default")
      (node (ref "R2004") (pin "2") (pinfunction "2_2") (pintype "passive"))
      (node (ref "R2008") (pin "1") (pinfunction "1_1") (pintype "passive"))
      (node (ref "U2000") (pin "12") (pinfunction "EN_12") (pintype "passive"))
    )
    (net (code "11") (name "Net-(U2000-FB)") (class "Default")
      (node (ref "R2016") (pin "2") (pinfunction "2_2") (pintype "passive"))
      (node (ref "R2017") (pin "2") (pinfunction "2_2") (pintype "passive"))
      (node (ref "R2018") (pin "1") (pinfunction "1_1") (pintype "passive"))
      (node (ref "U2000") (pin "11") (pinfunction "FB_11") (pintype "passive"))
    )
    (net (code "12") (name "Net-(U2000-MODE)") (class "Default")
      (node (ref "R2019") (pin "2") (pinfunction "2_2") (pintype "passive"))
      (node (ref "R2020") (pin "1") (pinfunction "1_1") (pintype "passive"))
      (node (ref "U2000") (pin "6") (pinfunction "MODE_6") (pintype "passive"))
    )
    (net (code "13") (name "Net-(U2000-PG)") (class "Default")
      (node (ref "R2009") (pin "2") (pinfunction "2_2") (pintype "passive"))
      (node (ref "U2000") (pin "3") (pinfunction "PG_3") (pintype "passive"))
    )
    (net (code "14") (name "Net-(U2000-SW)") (class "Default")
      (node (ref "L2000") (pin "1") (pinfunction "1_1") (pintype "passive"))
      (node (ref "U2000") (pin "7") (pinfunction "SW_7") (pintype "passive"))
    )
    (net (code "15") (name "Net-(U2000-VCC)") (class "Default")
      (node (ref "C2019") (pin "1") (pinfunction "1_1") (pintype "passive"))
      (node (ref "R2009") (pin "1") (pinfunction "1_1") (pintype "passive"))
      (node (ref "R2019") (pin "1") (pinfunction "1_1") (pintype "passive"))
      (node (ref "U2000") (pin "9") (pinfunction "VCC_9") (pintype "passive"))
    )
    (net (code "16") (name "Net-(U2001-EN)") (class "Default")
      (node (ref "C2025") (pin "1") (pinfunction "1_1") (pintype "passive"))
      (node (ref "R2011") (pin "2") (pinfunction "2_2") (pintype "passive"))
      (node (ref "U2001") (pin "1") (pinfunction "EN_1") (pintype "passive"))
    )
    (net (code "17") (name "Net-(U2001-FB{slash}OUT)") (class "Default")
      (node (ref "C2021") (pin "2") (pinfunction "2_2") (pintype "passive"))
      (node (ref "R2012") (pin "2") (pinfunction "2_2") (pintype "passive"))
      (node (ref "R2013") (pin "1") (pinfunction "1_1") (pintype "passive"))
      (node (ref "U2001") (pin "5") (pinfunction "FB/OUT_5") (pintype "passive"))
    )
    (net (code "18") (name "Net-(U2001-LX)") (class "Default")
      (node (ref "L2001") (pin "1") (pinfunction "1_1") (pintype "passive"))
      (node (ref "U2001") (pin "3") (pinfunction "LX_3") (pintype "passive"))
    )
    (net (code "19") (name "Net-(U2002-BS)") (class "Default")
      (node (ref "C2029") (pin "1") (pinfunction "1_1") (pintype "passive"))
      (node (ref "U2002") (pin "1") (pinfunction "BS_1") (pintype "passive"))
    )
    (net (code "20") (name "Net-(U2002-EN)") (class "Default")
      (node (ref "C2030") (pin "1") (pinfunction "1_1") (pintype "passive"))
      (node (ref "R2021") (pin "2") (pinfunction "2_2") (pintype "passive"))
      (node (ref "U2002") (pin "4") (pinfunction "EN_4") (pintype "passive"))
    )
    (net (code "21") (name "Net-(U2002-FB{slash}OUT)") (class "Default")
      (node (ref "C2031") (pin "2") (pinfunction "2_2") (pintype "passive"))
      (node (ref "R2022") (pin "2") (pinfunction "2_2") (pintype "passive"))
      (node (ref "R2023") (pin "1") (pinfunction "1_1") (pintype "passive"))
      (node (ref "U2002") (pin "3") (pinfunction "FB/OUT_3") (pintype "passive"))
    )
    (net (code "22") (name "Net-(U2002-LX)") (class "Default")
      (node (ref "C2029") (pin "2") (pinfunction "2_2") (pintype "passive"))
      (node (ref "L2002") (pin "1") (pinfunction "1_1") (pintype "passive"))
      (node (ref "U2002") (pin "6") (pinfunction "LX_6") (pintype "passive"))
    )
    (net (code "23") (name "PMIC_EXT_EN_OUT") (class "Default")
      (node (ref "R2011") (pin "1") (pinfunction "1_1") (pintype "passive"))
      (node (ref "R2021") (pin "1") (pinfunction "1_1") (pintype "passive"))
    )
    (net (code "24") (name "VCC4V0_SYS") (class "Default")
      (node (ref "C2015") (pin "1") (pinfunction "1_1") (pintype "passive"))
      (node (ref "C2017") (pin "1") (pinfunction "1_1") (pintype "passive"))
      (node (ref "C2020") (pin "1") (pinfunction "1_1") (pintype "passive"))
      (node (ref "R2006") (pin "2") (pinfunction "2_2") (pintype "passive"))
      (node (ref "U2000") (pin "5") (pinfunction "VOUT_5") (pintype "passive"))
      (node (ref "U2001") (pin "4") (pinfunction "VIN_4") (pintype "passive"))
    )
    (net (code "25") (name "VCC4V0_SYS_P") (class "Default")
      (node (ref "C2011") (pin "1") (pinfunction "1_1") (pintype "passive"))
      (node (ref "C2012") (pin "1") (pinfunction "1_1") (pintype "passive"))
      (node (ref "C2013") (pin "1") (pinfunction "1_1") (pintype "passive"))
      (node (ref "C2014") (pin "1") (pinfunction "1_1") (pintype "passive"))
      (node (ref "C2026") (pin "2") (pinfunction "2_2") (pintype "passive"))
      (node (ref "L2000") (pin "2") (pinfunction "2_2") (pintype "passive"))
      (node (ref "R2006") (pin "1") (pinfunction "1_1") (pintype "passive"))
      (node (ref "R2007") (pin "1") (pinfunction "1_1") (pintype "passive"))
      (node (ref "R2017") (pin "1") (pinfunction "1_1") (pintype "passive"))
    )
    (net (code "26") (name "VCC5V0_SYS") (class "Default")
      (node (ref "C2035") (pin "1") (pinfunction "1_1") (pintype "passive"))
      (node (ref "R2001") (pin "1") (pinfunction "1_1") (pintype "passive"))
      (node (ref "R2024") (pin "2") (pinfunction "2_2") (pintype "passive"))
    )
    (net (code "27") (name "VCC5V0_SYS_P") (class "Default")
      (node (ref "C2031") (pin "1") (pinfunction "1_1") (pintype "passive"))
      (node (ref "C2032") (pin "1") (pinfunction "1_1") (pintype "passive"))
      (node (ref "C2033") (pin "1") (pinfunction "1_1") (pintype "passive"))
      (node (ref "C2034") (pin "1") (pinfunction "1_1") (pintype "passive"))
      (node (ref "L2002") (pin "2") (pinfunction "2_2") (pintype "passive"))
      (node (ref "R2022") (pin "1") (pinfunction "1_1") (pintype "passive"))
      (node (ref "R2024") (pin "1") (pinfunction "1_1") (pintype "passive"))
    )
    (net (code "28") (name "VCC12VDC") (class "Default")
      (node (ref "F2000") (pin "1") (pinfunction "1_1") (pintype "passive"))
      (node (ref "J2000") (pin "1") (pinfunction "1_1") (pintype "passive"))
      (node (ref "J2001") (pin "3") (pinfunction "12V_1_3") (pintype "passive"))
      (node (ref "J2001") (pin "4") (pinfunction "12V_2_4") (pintype "passive"))
      (node (ref "R2000") (pin "1") (pinfunction "1_1") (pintype "passive"))
    )
    (net (code "29") (name "VCC12V_DCIN") (class "Default")
      (node (ref "C2000") (pin "1") (pinfunction "1_1") (pintype "passive"))
      (node (ref "C2001") (pin "1") (pinfunction "1_1") (pintype "passive"))
      (node (ref "C2007") (pin "1") (pinfunction "1_1") (pintype "passive"))
      (node (ref "C2009") (pin "1") (pinfunction "1_1") (pintype "passive"))
      (node (ref "C2010") (pin "1") (pinfunction "1_1") (pintype "passive"))
      (node (ref "C2027") (pin "1") (pinfunction "1_1") (pintype "passive"))
      (node (ref "C2028") (pin "1") (pinfunction "1_1") (pintype "passive"))
      (node (ref "D2000") (pin "2") (pinfunction "K_2") (pintype "passive"))
      (node (ref "F2000") (pin "2") (pinfunction "2_2") (pintype "passive"))
      (node (ref "R2002") (pin "1") (pinfunction "1_1") (pintype "passive"))
      (node (ref "R2003") (pin "1") (pinfunction "1_1") (pintype "passive"))
      (node (ref "R2004") (pin "1") (pinfunction "1_1") (pintype "passive"))
      (node (ref "U2000") (pin "1") (pinfunction "VIN_1") (pintype "passive"))
      (node (ref "U2002") (pin "5") (pinfunction "VIN_5") (pintype "passive"))
    )
    (net (code "30") (name "VCC_1V1_NLDO") (class "Default")
      (node (ref "C2024") (pin "1") (pinfunction "1_1") (pintype "passive"))
      (node (ref "R2010") (pin "2") (pinfunction "2_2") (pintype "passive"))
      (node (ref "R2014") (pin "2") (pinfunction "2_2") (pintype "passive"))
    )
    (net (code "31") (name "VCC_1V1_NLDO_P") (class "Default")
      (node (ref "C2021") (pin "1") (pinfunction "1_1") (pintype "passive"))
      (node (ref "C2022") (pin "1") (pinfunction "1_1") (pintype "passive"))
      (node (ref "C2023") (pin "1") (pinfunction "1_1") (pintype "passive"))
      (node (ref "L2001") (pin "2") (pinfunction "2_2") (pintype "passive"))
      (node (ref "R2010") (pin "1") (pinfunction "1_1") (pintype "passive"))
      (node (ref "R2012") (pin "1") (pinfunction "1_1") (pintype "passive"))
    )
    (net (code "32") (name "VCC_2V0_PLDO") (class "Default")
      (node (ref "R2014") (pin "1") (pinfunction "1_1") (pintype "passive"))
    )
    (net (code "33") (name "unconnected-(U2000-NC-Pad4)") (class "Default")
      (node (ref "U2000") (pin "4") (pinfunction "NC_4") (pintype "passive+no_connect"))
    )
  )
)
